# LED_Control_A4-A7.net
KiCad netlist of a schematic drawn in Altium Designer
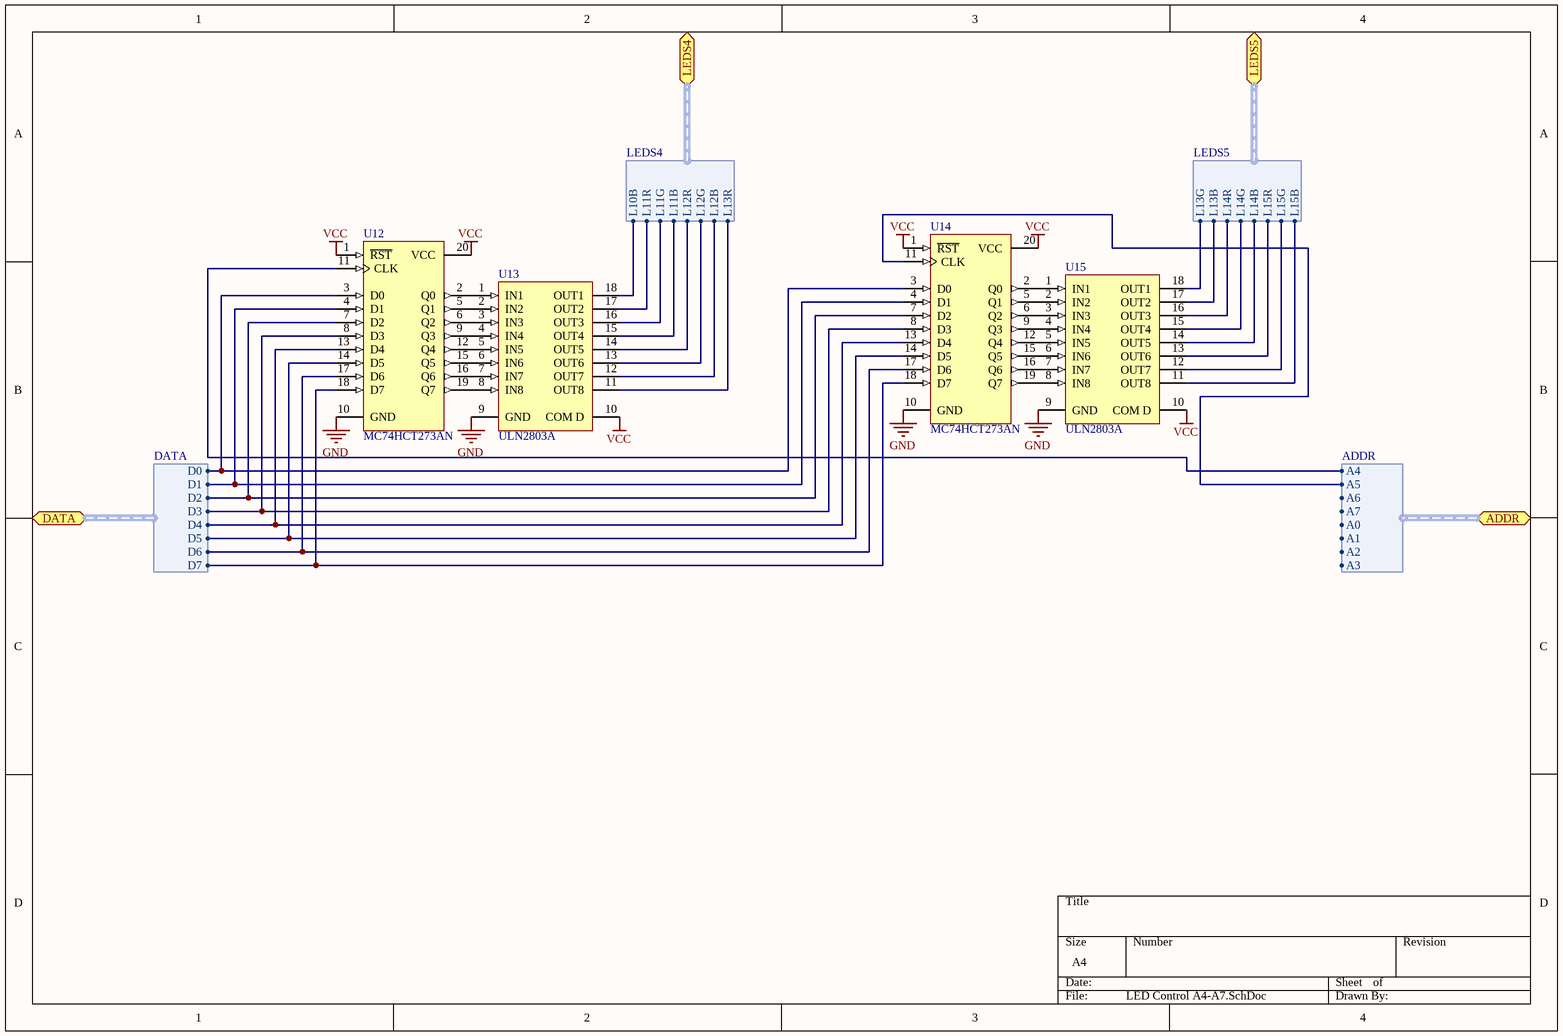
[diagram p0: LED Control A4-A7.SchDoc]

(export (version "E")
  (design (tool "Eeschema 10.0.6"))
  (components
    (comp (ref "U12")
      (value "MC74HCT273AN")
      (footprint "738-03")
      (description "Octal D-Type Flip-Flop with Common Clock and Reset with LSTTL-Compatible Inputs")
      (fields (field (name "PUBLISHER") "Altium Limited"))
      (libsource (lib "ON Semi Logic Flip-Flop") (part "MC74HCT273AN"))
    )
    (comp (ref "U13")
      (value "ULN2803A")
      (footprint "DIP18")
      (description "Eight Darlington Array")
      (fields (field (name "PUBLISHER") "Altium Limited"))
      (libsource (lib "ST Interface Darlington Driver") (part "ULN2803A"))
    )
    (comp (ref "U14")
      (value "MC74HCT273AN")
      (footprint "738-03")
      (description "Octal D-Type Flip-Flop with Common Clock and Reset with LSTTL-Compatible Inputs")
      (fields (field (name "PUBLISHER") "Altium Limited"))
      (libsource (lib "ON Semi Logic Flip-Flop") (part "MC74HCT273AN"))
    )
    (comp (ref "U15")
      (value "ULN2803A")
      (footprint "DIP18")
      (description "Eight Darlington Array")
      (fields (field (name "PUBLISHER") "Altium Limited"))
      (libsource (lib "ST Interface Darlington Driver") (part "ULN2803A"))
    )
  )
  (nets
    (net (code "5") (name "/A4") (class "Default")
      (node (ref "U12") (pin "11") (pinfunction "CLK_11") (pintype "input"))
    )
    (net (code "6") (name "/A5") (class "Default")
      (node (ref "U14") (pin "11") (pinfunction "CLK_11") (pintype "input"))
    )
    (net (code "7") (name "/D0") (class "Default")
      (node (ref "U12") (pin "3") (pinfunction "D0_3") (pintype "input"))
      (node (ref "U14") (pin "3") (pinfunction "D0_3") (pintype "input"))
    )
    (net (code "8") (name "/D1") (class "Default")
      (node (ref "U12") (pin "4") (pinfunction "D1_4") (pintype "input"))
      (node (ref "U14") (pin "4") (pinfunction "D1_4") (pintype "input"))
    )
    (net (code "9") (name "/D2") (class "Default")
      (node (ref "U12") (pin "7") (pinfunction "D2_7") (pintype "input"))
      (node (ref "U14") (pin "7") (pinfunction "D2_7") (pintype "input"))
    )
    (net (code "10") (name "/D3") (class "Default")
      (node (ref "U12") (pin "8") (pinfunction "D3_8") (pintype "input"))
      (node (ref "U14") (pin "8") (pinfunction "D3_8") (pintype "input"))
    )
    (net (code "11") (name "/D4") (class "Default")
      (node (ref "U12") (pin "13") (pinfunction "D4_13") (pintype "input"))
      (node (ref "U14") (pin "13") (pinfunction "D4_13") (pintype "input"))
    )
    (net (code "12") (name "/D5") (class "Default")
      (node (ref "U12") (pin "14") (pinfunction "D5_14") (pintype "input"))
      (node (ref "U14") (pin "14") (pinfunction "D5_14") (pintype "input"))
    )
    (net (code "13") (name "/D6") (class "Default")
      (node (ref "U12") (pin "17") (pinfunction "D6_17") (pintype "input"))
      (node (ref "U14") (pin "17") (pinfunction "D6_17") (pintype "input"))
    )
    (net (code "14") (name "/D7") (class "Default")
      (node (ref "U12") (pin "18") (pinfunction "D7_18") (pintype "input"))
      (node (ref "U14") (pin "18") (pinfunction "D7_18") (pintype "input"))
    )
    (net (code "15") (name "/L10B") (class "Default")
      (node (ref "U13") (pin "18") (pinfunction "OUT1_18") (pintype "open_collector"))
    )
    (net (code "16") (name "/L11B") (class "Default")
      (node (ref "U13") (pin "15") (pinfunction "OUT4_15") (pintype "open_collector"))
    )
    (net (code "17") (name "/L11G") (class "Default")
      (node (ref "U13") (pin "16") (pinfunction "OUT3_16") (pintype "open_collector"))
    )
    (net (code "18") (name "/L11R") (class "Default")
      (node (ref "U13") (pin "17") (pinfunction "OUT2_17") (pintype "open_collector"))
    )
    (net (code "19") (name "/L12B") (class "Default")
      (node (ref "U13") (pin "12") (pinfunction "OUT7_12") (pintype "open_collector"))
    )
    (net (code "20") (name "/L12G") (class "Default")
      (node (ref "U13") (pin "13") (pinfunction "OUT6_13") (pintype "open_collector"))
    )
    (net (code "21") (name "/L12R") (class "Default")
      (node (ref "U13") (pin "14") (pinfunction "OUT5_14") (pintype "open_collector"))
    )
    (net (code "22") (name "/L13B") (class "Default")
      (node (ref "U15") (pin "17") (pinfunction "OUT2_17") (pintype "open_collector"))
    )
    (net (code "23") (name "/L13G") (class "Default")
      (node (ref "U15") (pin "18") (pinfunction "OUT1_18") (pintype "open_collector"))
    )
    (net (code "24") (name "/L13R") (class "Default")
      (node (ref "U13") (pin "11") (pinfunction "OUT8_11") (pintype "open_collector"))
    )
    (net (code "25") (name "/L14B") (class "Default")
      (node (ref "U15") (pin "14") (pinfunction "OUT5_14") (pintype "open_collector"))
    )
    (net (code "26") (name "/L14G") (class "Default")
      (node (ref "U15") (pin "15") (pinfunction "OUT4_15") (pintype "open_collector"))
    )
    (net (code "27") (name "/L14R") (class "Default")
      (node (ref "U15") (pin "16") (pinfunction "OUT3_16") (pintype "open_collector"))
    )
    (net (code "28") (name "/L15B") (class "Default")
      (node (ref "U15") (pin "11") (pinfunction "OUT8_11") (pintype "open_collector"))
    )
    (net (code "29") (name "/L15G") (class "Default")
      (node (ref "U15") (pin "12") (pinfunction "OUT7_12") (pintype "open_collector"))
    )
    (net (code "30") (name "/L15R") (class "Default")
      (node (ref "U15") (pin "13") (pinfunction "OUT6_13") (pintype "open_collector"))
    )
    (net (code "35") (name "GND") (class "Default")
      (node (ref "U12") (pin "10") (pinfunction "GND_10") (pintype "power_in"))
      (node (ref "U13") (pin "9") (pinfunction "GND_9") (pintype "power_in"))
      (node (ref "U14") (pin "10") (pinfunction "GND_10") (pintype "power_in"))
      (node (ref "U15") (pin "9") (pinfunction "GND_9") (pintype "power_in"))
    )
    (net (code "36") (name "Net-(U12-Q0)") (class "Default")
      (node (ref "U12") (pin "2") (pinfunction "Q0_2") (pintype "output"))
      (node (ref "U13") (pin "1") (pinfunction "IN1_1") (pintype "input"))
    )
    (net (code "37") (name "Net-(U12-Q1)") (class "Default")
      (node (ref "U12") (pin "5") (pinfunction "Q1_5") (pintype "output"))
      (node (ref "U13") (pin "2") (pinfunction "IN2_2") (pintype "input"))
    )
    (net (code "38") (name "Net-(U12-Q2)") (class "Default")
      (node (ref "U12") (pin "6") (pinfunction "Q2_6") (pintype "output"))
      (node (ref "U13") (pin "3") (pinfunction "IN3_3") (pintype "input"))
    )
    (net (code "39") (name "Net-(U12-Q3)") (class "Default")
      (node (ref "U12") (pin "9") (pinfunction "Q3_9") (pintype "output"))
      (node (ref "U13") (pin "4") (pinfunction "IN4_4") (pintype "input"))
    )
    (net (code "40") (name "Net-(U12-Q4)") (class "Default")
      (node (ref "U12") (pin "12") (pinfunction "Q4_12") (pintype "output"))
      (node (ref "U13") (pin "5") (pinfunction "IN5_5") (pintype "input"))
    )
    (net (code "41") (name "Net-(U12-Q5)") (class "Default")
      (node (ref "U12") (pin "15") (pinfunction "Q5_15") (pintype "output"))
      (node (ref "U13") (pin "6") (pinfunction "IN6_6") (pintype "input"))
    )
    (net (code "42") (name "Net-(U12-Q6)") (class "Default")
      (node (ref "U12") (pin "16") (pinfunction "Q6_16") (pintype "output"))
      (node (ref "U13") (pin "7") (pinfunction "IN7_7") (pintype "input"))
    )
    (net (code "43") (name "Net-(U12-Q7)") (class "Default")
      (node (ref "U12") (pin "19") (pinfunction "Q7_19") (pintype "output"))
      (node (ref "U13") (pin "8") (pinfunction "IN8_8") (pintype "input"))
    )
    (net (code "44") (name "Net-(U14-Q0)") (class "Default")
      (node (ref "U14") (pin "2") (pinfunction "Q0_2") (pintype "output"))
      (node (ref "U15") (pin "1") (pinfunction "IN1_1") (pintype "input"))
    )
    (net (code "45") (name "Net-(U14-Q1)") (class "Default")
      (node (ref "U14") (pin "5") (pinfunction "Q1_5") (pintype "output"))
      (node (ref "U15") (pin "2") (pinfunction "IN2_2") (pintype "input"))
    )
    (net (code "46") (name "Net-(U14-Q2)") (class "Default")
      (node (ref "U14") (pin "6") (pinfunction "Q2_6") (pintype "output"))
      (node (ref "U15") (pin "3") (pinfunction "IN3_3") (pintype "input"))
    )
    (net (code "47") (name "Net-(U14-Q3)") (class "Default")
      (node (ref "U14") (pin "9") (pinfunction "Q3_9") (pintype "output"))
      (node (ref "U15") (pin "4") (pinfunction "IN4_4") (pintype "input"))
    )
    (net (code "48") (name "Net-(U14-Q4)") (class "Default")
      (node (ref "U14") (pin "12") (pinfunction "Q4_12") (pintype "output"))
      (node (ref "U15") (pin "5") (pinfunction "IN5_5") (pintype "input"))
    )
    (net (code "49") (name "Net-(U14-Q5)") (class "Default")
      (node (ref "U14") (pin "15") (pinfunction "Q5_15") (pintype "output"))
      (node (ref "U15") (pin "6") (pinfunction "IN6_6") (pintype "input"))
    )
    (net (code "50") (name "Net-(U14-Q6)") (class "Default")
      (node (ref "U14") (pin "16") (pinfunction "Q6_16") (pintype "output"))
      (node (ref "U15") (pin "7") (pinfunction "IN7_7") (pintype "input"))
    )
    (net (code "51") (name "Net-(U14-Q7)") (class "Default")
      (node (ref "U14") (pin "19") (pinfunction "Q7_19") (pintype "output"))
      (node (ref "U15") (pin "8") (pinfunction "IN8_8") (pintype "input"))
    )
    (net (code "52") (name "VCC") (class "Default")
      (node (ref "U12") (pin "1") (pinfunction "~{RST}_1") (pintype "input"))
      (node (ref "U12") (pin "20") (pinfunction "VCC_20") (pintype "power_in"))
      (node (ref "U13") (pin "10") (pinfunction "COM_D_10") (pintype "passive"))
      (node (ref "U14") (pin "1") (pinfunction "~{RST}_1") (pintype "input"))
      (node (ref "U14") (pin "20") (pinfunction "VCC_20") (pintype "power_in"))
      (node (ref "U15") (pin "10") (pinfunction "COM_D_10") (pintype "passive"))
    )
  )
)
